# Sheet2_USB-PD.net
KiCad netlist of a schematic drawn in Altium Designer
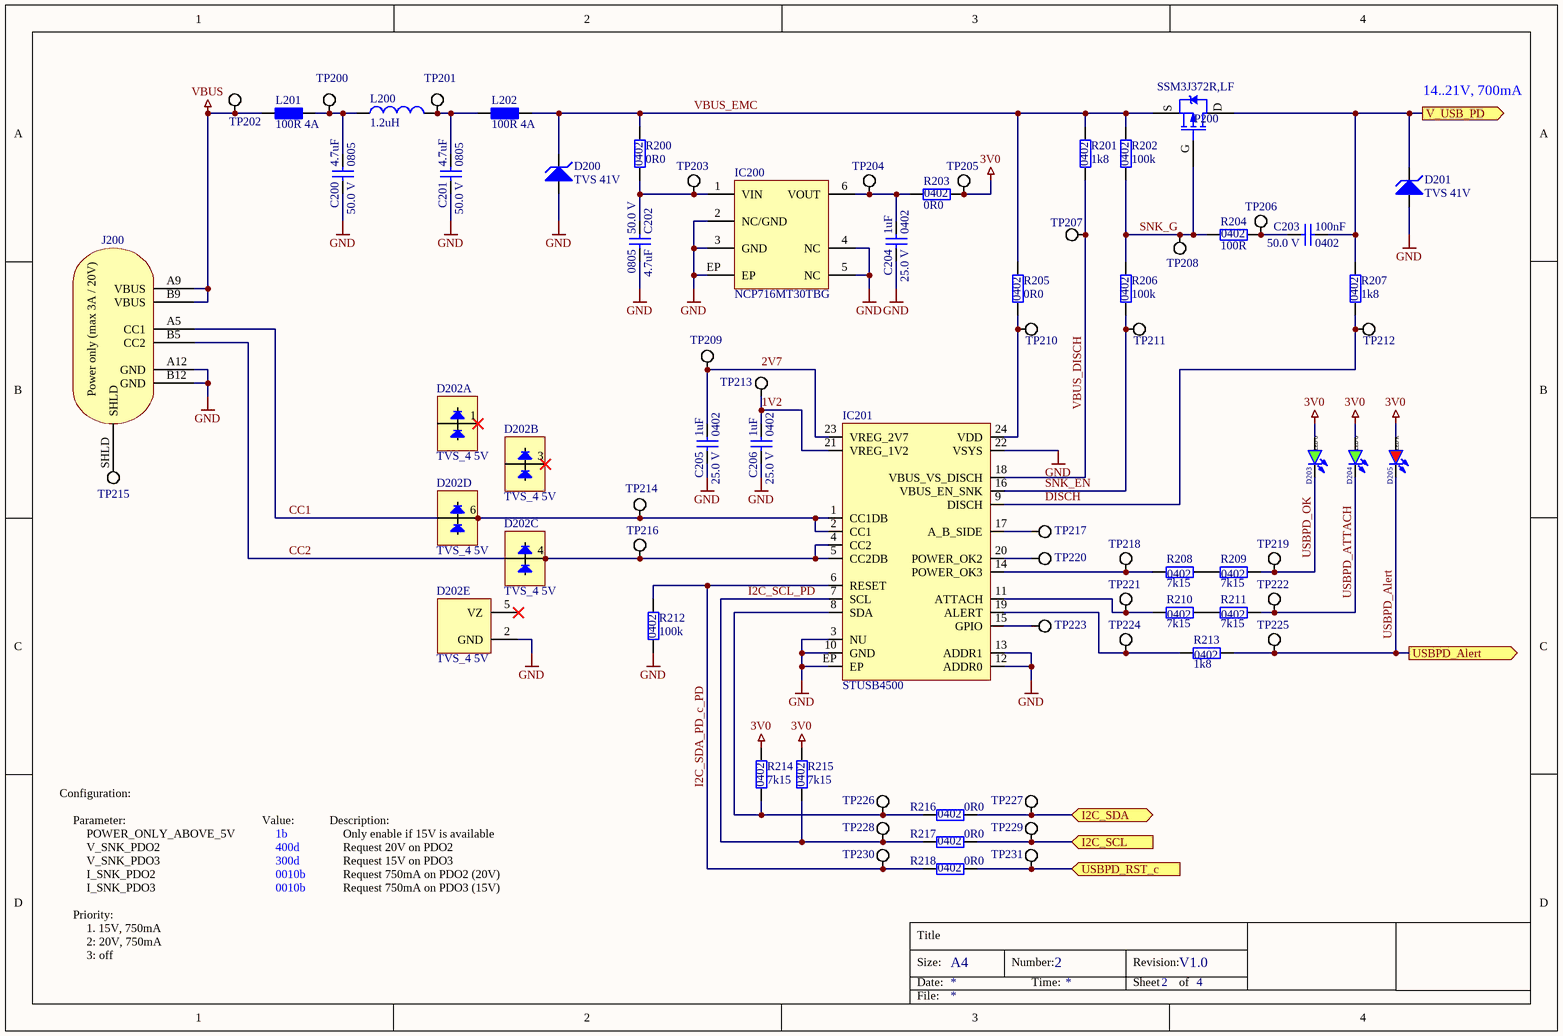
[diagram p0: Sheet2_USB-PD.SchDoc]

(export (version "E")
  (design (tool "Eeschema 10.0.6"))
  (components
    (comp (ref "C200")
      (value "C 4.7uF 0805 50V")
      (footprint "0805")
      (description "CAP CER 4.7UF 50V X5R 0805")
      (fields
        (field (name "MANUFACTURER") "Samsung Electro-Mechanics")
        (field (name "MANUFACTURER PART NUMBER") "CL21A475KBQNNNE")
        (field (name "CAPACITANCE") "4.7uF")
        (field (name "VOLTAGE") "50.0 V")
      )
      (libsource (lib "CS_Part_Library") (part "CAP_4.7uF_50V_0805"))
    )
    (comp (ref "C201")
      (value "C 4.7uF 0805 50V")
      (footprint "0805")
      (description "CAP CER 4.7UF 50V X5R 0805")
      (fields
        (field (name "MANUFACTURER") "Samsung Electro-Mechanics")
        (field (name "MANUFACTURER PART NUMBER") "CL21A475KBQNNNE")
        (field (name "CAPACITANCE") "4.7uF")
        (field (name "VOLTAGE") "50.0 V")
      )
      (libsource (lib "CS_Part_Library") (part "CAP_4.7uF_50V_0805"))
    )
    (comp (ref "C202")
      (value "C 4.7uF 0805 50V")
      (footprint "0805")
      (description "CAP CER 4.7UF 50V X5R 0805")
      (fields
        (field (name "MANUFACTURER") "Samsung Electro-Mechanics")
        (field (name "MANUFACTURER PART NUMBER") "CL21A475KBQNNNE")
        (field (name "CAPACITANCE") "4.7uF")
        (field (name "VOLTAGE") "50.0 V")
      )
      (libsource (lib "CS_Part_Library") (part "CAP_4.7uF_50V_0805"))
    )
    (comp (ref "C203")
      (value "C 100nF 0402 50V")
      (footprint "0402")
      (description "CAP CER 0.1UF 50V X7R 0402")
      (fields
        (field (name "MANUFACTURER") "Murata Electronics")
        (field (name "MANUFACTURER PART NUMBER") "GRM155R71H104KE14J")
        (field (name "CAPACITANCE") "100nF")
        (field (name "VOLTAGE") "50.0 V")
      )
      (libsource (lib "CS_Part_Library") (part "CAP_100nF_50V_0402"))
    )
    (comp (ref "C204")
      (value "C 1uF 0402 25V")
      (footprint "0402")
      (description "CAP CER 1UF 25V X5R 0402")
      (fields
        (field (name "MANUFACTURER") "Taiyo Yuden")
        (field (name "MANUFACTURER PART NUMBER") "TMK105BJ105MV-F")
        (field (name "CAPACITANCE") "1uF")
        (field (name "VOLTAGE") "25.0 V")
      )
      (libsource (lib "CS_Part_Library") (part "CAP_1uF_25V_0402"))
    )
    (comp (ref "C205")
      (value "C 1uF 0402 25V")
      (footprint "0402")
      (description "CAP CER 1UF 25V X5R 0402")
      (fields
        (field (name "MANUFACTURER") "Taiyo Yuden")
        (field (name "MANUFACTURER PART NUMBER") "TMK105BJ105MV-F")
        (field (name "CAPACITANCE") "1uF")
        (field (name "VOLTAGE") "25.0 V")
      )
      (libsource (lib "CS_Part_Library") (part "CAP_1uF_25V_0402"))
    )
    (comp (ref "C206")
      (value "C 1uF 0402 25V")
      (footprint "0402")
      (description "CAP CER 1UF 25V X5R 0402")
      (fields
        (field (name "MANUFACTURER") "Taiyo Yuden")
        (field (name "MANUFACTURER PART NUMBER") "TMK105BJ105MV-F")
        (field (name "CAPACITANCE") "1uF")
        (field (name "VOLTAGE") "25.0 V")
      )
      (libsource (lib "CS_Part_Library") (part "CAP_1uF_25V_0402"))
    )
    (comp (ref "D200")
      (value "TVS 41V")
      (footprint "UDFN-2")
      (description "TVS DIODE 22VWM 41VC 1610")
      (fields
        (field (name "MANUFACTURER") "STMicroelectronics")
        (field (name "MANUFACTURER PART NUMBER") "ESDA25P35-1U1M")
      )
      (libsource (lib "Symbols") (part "D_SCH_41V_35A"))
    )
    (comp (ref "D201")
      (value "TVS 41V")
      (footprint "UDFN-2")
      (description "TVS DIODE 22VWM 41VC 1610")
      (fields
        (field (name "MANUFACTURER") "STMicroelectronics")
        (field (name "MANUFACTURER PART NUMBER") "ESDA25P35-1U1M")
      )
      (libsource (lib "Symbols") (part "D_SCH_41V_35A"))
    )
    (comp (ref "D202")
      (value "TVS_4 5V")
      (footprint "SOT-23-6")
      (description "TVS DIODE 5VWM 12.5VC SOT23-6")
      (fields
        (field (name "MANUFACTURER") "Comchip Technology")
        (field (name "MANUFACTURER PART NUMBER") "CPDT6-5V0UPC-HF")
      )
      (libsource (lib "CS_Part_Library") (part "D_TVS_U4_12V5"))
    )
    (comp (ref "D203")
      (value "LED G")
      (footprint "LED_0603")
      (description "LED GREEN DIFFUSED 0603 SMD")
      (fields
        (field (name "MANUFACTURER") "OSRAM Opto Semiconductors Inc.")
        (field (name "MANUFACTURER PART NUMBER") "LT Q39G-Q1OO-25-1")
      )
      (libsource (lib "CS_Part_Library") (part "D_LED_Green_0603"))
    )
    (comp (ref "D204")
      (value "LED G")
      (footprint "LED_0603")
      (description "LED GREEN DIFFUSED 0603 SMD")
      (fields
        (field (name "MANUFACTURER") "OSRAM Opto Semiconductors Inc.")
        (field (name "MANUFACTURER PART NUMBER") "LT Q39G-Q1OO-25-1")
      )
      (libsource (lib "CS_Part_Library") (part "D_LED_Green_0603"))
    )
    (comp (ref "D205")
      (value "LED R")
      (footprint "LED_0603")
      (description "LED RED DIFFUSED 0603 SMD")
      (fields
        (field (name "MANUFACTURER") "OSRAM Opto Semiconductors Inc.")
        (field (name "MANUFACTURER PART NUMBER") "LS Q976-NR-1")
      )
      (libsource (lib "CS_Part_Library") (part "D_LED_Red_0603"))
    )
    (comp (ref "IC200")
      (value "NCP716MT30TBG")
      (footprint "WDFN-6_EP")
      (description "IC REG LINEAR 3V 80MA 6WDFN")
      (fields (field (name "MANUFACTURER") "onsemi"))
      (libsource (lib "CS_Part_Library") (part "IC_Reg_NCP716MT30TBG"))
    )
    (comp (ref "IC201")
      (value "STUSB4500")
      (footprint "VFQFN-24")
      (description "IC USB CONTROLLER I2C 24QFN")
      (fields
        (field (name "MANUFACTURER") "STMicroelectronics")
        (field (name "MANUFACTURER PART NUMBER") "STUSB4500QTR")
      )
      (libsource (lib "CS_Part_Library") (part "IC_STUSB4500"))
    )
    (comp (ref "J200")
      (value "USB_C PWR")
      (footprint "J_TYPE-C-3_UJC-HP2-3")
      (description "TYPE C, 20 VDC, 3 A, RIGHT ANGLE")
      (fields
        (field (name "MANUFACTURER") "CUI Devices")
        (field (name "MANUFACTURER PART NUMBER") "UJC-HP2-3-SMT-TR")
      )
      (libsource (lib "CS_Part_Library") (part "J_USB-C_3"))
    )
    (comp (ref "L200")
      (value "L 1.2uH 3.9A")
      (footprint "L_3020")
      (description "FIXED IND 1.2UH 3.9A 36 MOHM SMD")
      (fields
        (field (name "MANUFACTURER") "Würth Elektronik")
        (field (name "MANUFACTURER PART NUMBER") "74438336012")
        (field (name "INDUCTANCE") "1.2uH")
      )
      (libsource (lib "CS_Part_Library") (part "L_1.2uH_3.9A"))
    )
    (comp (ref "L201")
      (value "L Ferrite 100R 4A")
      (footprint "L_1206")
      (description "FIXED IND 100 4000MA 1206")
      (fields
        (field (name "MANUFACTURER") "Eaton - Electronics Division")
        (field (name "MANUFACTURER PART NUMBER") "MFBM1V3216-101-R")
        (field (name "INDUCTANCE") "100R 4A")
      )
      (libsource (lib "CS_Part_Library") (part "L_100R_4A"))
    )
    (comp (ref "L202")
      (value "L Ferrite 100R 4A")
      (footprint "L_1206")
      (description "FIXED IND 100 4000MA 1206")
      (fields
        (field (name "MANUFACTURER") "Eaton - Electronics Division")
        (field (name "MANUFACTURER PART NUMBER") "MFBM1V3216-101-R")
        (field (name "INDUCTANCE") "100R 4A")
      )
      (libsource (lib "CS_Part_Library") (part "L_100R_4A"))
    )
    (comp (ref "P200")
      (value "P PMOS 30V 6A")
      (footprint "SOT-23-3-F")
      (description "MOSFET P-CH 30V 6A SOT23F")
      (fields
        (field (name "MANUFACTURER") "Toshiba Semiconductor and Storage")
        (field (name "MANUFACTURER PART NUMBER") "SSM3J372R,LF")
      )
      (libsource (lib "CS_Part_Library") (part "P_PCH_30V_1W"))
    )
    (comp (ref "R200")
      (value "R 0R0 0402")
      (footprint "0402")
      (description "RES 0 OHM JUMPER 1/16W 0402")
      (fields
        (field (name "MANUFACTURER") "Stackpole Electronics Inc")
        (field (name "MANUFACTURER PART NUMBER") "RMCF0402ZT0R00")
        (field (name "RESISTANCE") "0R0")
      )
      (libsource (lib "CS_Part_Library") (part "R_0R0_0402"))
    )
    (comp (ref "R201")
      (value "R 1k8 0402")
      (footprint "0402")
      (description "RES 1.8K OHM 1% 1/16W 0402")
      (fields
        (field (name "MANUFACTURER") "Stackpole Electronics Inc")
        (field (name "MANUFACTURER PART NUMBER") "RMCF0402FT1K80")
        (field (name "RESISTANCE") "1k8")
      )
      (libsource (lib "CS_Part_Library") (part "R_1k8_0402"))
    )
    (comp (ref "R202")
      (value "R 100k 0402")
      (footprint "0402")
      (description "RES 100K OHM 5% 1/16W 0402")
      (fields
        (field (name "MANUFACTURER") "YAGEO")
        (field (name "MANUFACTURER PART NUMBER") "RC0402JR-07100KL")
        (field (name "RESISTANCE") "100k")
      )
      (libsource (lib "CS_Part_Library") (part "R_100k_0402"))
    )
    (comp (ref "R203")
      (value "R 0R0 0402")
      (footprint "0402")
      (description "RES 0 OHM JUMPER 1/16W 0402")
      (fields
        (field (name "MANUFACTURER") "Stackpole Electronics Inc")
        (field (name "MANUFACTURER PART NUMBER") "RMCF0402ZT0R00")
        (field (name "RESISTANCE") "0R0")
      )
      (libsource (lib "") (part "R_0R0_0402_1"))
    )
    (comp (ref "R204")
      (value "R 100R 0402")
      (footprint "0402")
      (description "RES 100 OHM 1% 1/16W 0402")
      (fields
        (field (name "MANUFACTURER") "Stackpole Electronics Inc")
        (field (name "MANUFACTURER PART NUMBER") "RMCF0402FT100R")
        (field (name "RESISTANCE") "100R")
      )
      (libsource (lib "CS_Part_Library") (part "R_100R_0402"))
    )
    (comp (ref "R205")
      (value "R 0R0 0402")
      (footprint "0402")
      (description "RES 0 OHM JUMPER 1/16W 0402")
      (fields
        (field (name "MANUFACTURER") "Stackpole Electronics Inc")
        (field (name "MANUFACTURER PART NUMBER") "RMCF0402ZT0R00")
        (field (name "RESISTANCE") "0R0")
      )
      (libsource (lib "CS_Part_Library") (part "R_0R0_0402"))
    )
    (comp (ref "R206")
      (value "R 100k 0402")
      (footprint "0402")
      (description "RES 100K OHM 5% 1/16W 0402")
      (fields
        (field (name "MANUFACTURER") "YAGEO")
        (field (name "MANUFACTURER PART NUMBER") "RC0402JR-07100KL")
        (field (name "RESISTANCE") "100k")
      )
      (libsource (lib "CS_Part_Library") (part "R_100k_0402"))
    )
    (comp (ref "R207")
      (value "R 1k8 0402")
      (footprint "0402")
      (description "RES 1.8K OHM 1% 1/16W 0402")
      (fields
        (field (name "MANUFACTURER") "Stackpole Electronics Inc")
        (field (name "MANUFACTURER PART NUMBER") "RMCF0402FT1K80")
        (field (name "RESISTANCE") "1k8")
      )
      (libsource (lib "CS_Part_Library") (part "R_1k8_0402"))
    )
    (comp (ref "R208")
      (value "R 7k15 0402")
      (footprint "0402")
      (description "RES 7.15K OHM 1% 1/16W 0402")
      (fields
        (field (name "MANUFACTURER") "Stackpole Electronics Inc")
        (field (name "MANUFACTURER PART NUMBER") "RMCF0402FT7K15")
        (field (name "RESISTANCE") "7k15")
      )
      (libsource (lib "CS_Part_Library") (part "R_7k15_0402"))
    )
    (comp (ref "R209")
      (value "R 7k15 0402")
      (footprint "0402")
      (description "RES 7.15K OHM 1% 1/16W 0402")
      (fields
        (field (name "MANUFACTURER") "Stackpole Electronics Inc")
        (field (name "MANUFACTURER PART NUMBER") "RMCF0402FT7K15")
        (field (name "RESISTANCE") "7k15")
      )
      (libsource (lib "CS_Part_Library") (part "R_7k15_0402"))
    )
    (comp (ref "R210")
      (value "R 7k15 0402")
      (footprint "0402")
      (description "RES 7.15K OHM 1% 1/16W 0402")
      (fields
        (field (name "MANUFACTURER") "Stackpole Electronics Inc")
        (field (name "MANUFACTURER PART NUMBER") "RMCF0402FT7K15")
        (field (name "RESISTANCE") "7k15")
      )
      (libsource (lib "CS_Part_Library") (part "R_7k15_0402"))
    )
    (comp (ref "R211")
      (value "R 7k15 0402")
      (footprint "0402")
      (description "RES 7.15K OHM 1% 1/16W 0402")
      (fields
        (field (name "MANUFACTURER") "Stackpole Electronics Inc")
        (field (name "MANUFACTURER PART NUMBER") "RMCF0402FT7K15")
        (field (name "RESISTANCE") "7k15")
      )
      (libsource (lib "CS_Part_Library") (part "R_7k15_0402"))
    )
    (comp (ref "R212")
      (value "R 100k 0402")
      (footprint "0402")
      (description "RES 100K OHM 5% 1/16W 0402")
      (fields
        (field (name "MANUFACTURER") "YAGEO")
        (field (name "MANUFACTURER PART NUMBER") "RC0402JR-07100KL")
        (field (name "RESISTANCE") "100k")
      )
      (libsource (lib "CS_Part_Library") (part "R_100k_0402"))
    )
    (comp (ref "R213")
      (value "R 1k8 0402")
      (footprint "0402")
      (description "RES 1.8K OHM 1% 1/16W 0402")
      (fields
        (field (name "MANUFACTURER") "Stackpole Electronics Inc")
        (field (name "MANUFACTURER PART NUMBER") "RMCF0402FT1K80")
        (field (name "RESISTANCE") "1k8")
      )
      (libsource (lib "") (part "R_1k8_0402_1"))
    )
    (comp (ref "R214")
      (value "R 7k15 0402")
      (footprint "0402")
      (description "RES 7.15K OHM 1% 1/16W 0402")
      (fields
        (field (name "MANUFACTURER") "Stackpole Electronics Inc")
        (field (name "MANUFACTURER PART NUMBER") "RMCF0402FT7K15")
        (field (name "RESISTANCE") "7k15")
      )
      (libsource (lib "") (part "R_7k15_0402_1"))
    )
    (comp (ref "R215")
      (value "R 7k15 0402")
      (footprint "0402")
      (description "RES 7.15K OHM 1% 1/16W 0402")
      (fields
        (field (name "MANUFACTURER") "Stackpole Electronics Inc")
        (field (name "MANUFACTURER PART NUMBER") "RMCF0402FT7K15")
        (field (name "RESISTANCE") "7k15")
      )
      (libsource (lib "") (part "R_7k15_0402_1"))
    )
    (comp (ref "R216")
      (value "R 0R0 0402")
      (footprint "0402")
      (description "RES 0 OHM JUMPER 1/16W 0402")
      (fields
        (field (name "MANUFACTURER") "Stackpole Electronics Inc")
        (field (name "MANUFACTURER PART NUMBER") "RMCF0402ZT0R00")
        (field (name "RESISTANCE") "0R0")
      )
      (libsource (lib "") (part "R_0R0_0402_1"))
    )
    (comp (ref "R217")
      (value "R 0R0 0402")
      (footprint "0402")
      (description "RES 0 OHM JUMPER 1/16W 0402")
      (fields
        (field (name "MANUFACTURER") "Stackpole Electronics Inc")
        (field (name "MANUFACTURER PART NUMBER") "RMCF0402ZT0R00")
        (field (name "RESISTANCE") "0R0")
      )
      (libsource (lib "") (part "R_0R0_0402_1"))
    )
    (comp (ref "R218")
      (value "R 0R0 0402")
      (footprint "0402")
      (description "RES 0 OHM JUMPER 1/16W 0402")
      (fields
        (field (name "MANUFACTURER") "Stackpole Electronics Inc")
        (field (name "MANUFACTURER PART NUMBER") "RMCF0402ZT0R00")
        (field (name "RESISTANCE") "0R0")
      )
      (libsource (lib "") (part "R_0R0_0402_1"))
    )
    (comp (ref "TP200")
      (value "TP")
      (footprint "TP_1mm")
      (description "Test Point 1mm")
      (libsource (lib "Symbols") (part "TP_1mm"))
    )
    (comp (ref "TP201")
      (value "TP")
      (footprint "TP_1mm")
      (description "Test Point 1mm")
      (libsource (lib "Symbols") (part "TP_1mm"))
    )
    (comp (ref "TP202")
      (value "TP")
      (footprint "TP_1mm")
      (description "Test Point 1mm")
      (libsource (lib "CS_Part_Library") (part "TP_1mm"))
    )
    (comp (ref "TP203")
      (value "TP")
      (footprint "TP_1mm")
      (description "Test Point 1mm")
      (libsource (lib "CS_Part_Library") (part "TP_1mm"))
    )
    (comp (ref "TP204")
      (value "TP")
      (footprint "TP_1mm")
      (description "Test Point 1mm")
      (libsource (lib "CS_Part_Library") (part "TP_1mm"))
    )
    (comp (ref "TP205")
      (value "TP")
      (footprint "TP_1mm")
      (description "Test Point 1mm")
      (libsource (lib "CS_Part_Library") (part "TP_1mm"))
    )
    (comp (ref "TP206")
      (value "TP")
      (footprint "TP_1mm")
      (description "Test Point 1mm")
      (libsource (lib "CS_Part_Library") (part "TP_1mm"))
    )
    (comp (ref "TP207")
      (value "TP")
      (footprint "TP_1mm")
      (description "Test Point 1mm")
      (libsource (lib "CS_Part_Library") (part "TP_1mm"))
    )
    (comp (ref "TP208")
      (value "TP")
      (footprint "TP_1mm")
      (description "Test Point 1mm")
      (libsource (lib "CS_Part_Library") (part "TP_1mm"))
    )
    (comp (ref "TP209")
      (value "TP")
      (footprint "TP_1mm")
      (description "Test Point 1mm")
      (libsource (lib "CS_Part_Library") (part "TP_1mm"))
    )
    (comp (ref "TP210")
      (value "TP")
      (footprint "TP_1mm")
      (description "Test Point 1mm")
      (libsource (lib "CS_Part_Library") (part "TP_1mm"))
    )
    (comp (ref "TP211")
      (value "TP")
      (footprint "TP_1mm")
      (description "Test Point 1mm")
      (libsource (lib "CS_Part_Library") (part "TP_1mm"))
    )
    (comp (ref "TP212")
      (value "TP")
      (footprint "TP_1mm")
      (description "Test Point 1mm")
      (libsource (lib "CS_Part_Library") (part "TP_1mm"))
    )
    (comp (ref "TP213")
      (value "TP")
      (footprint "TP_1mm")
      (description "Test Point 1mm")
      (libsource (lib "CS_Part_Library") (part "TP_1mm"))
    )
    (comp (ref "TP214")
      (value "TP")
      (footprint "TP_1mm")
      (description "Test Point 1mm")
      (libsource (lib "CS_Part_Library") (part "TP_1mm"))
    )
    (comp (ref "TP215")
      (value "TP")
      (footprint "TP_1mm")
      (description "Test Point 1mm")
      (libsource (lib "CS_Part_Library") (part "TP_1mm"))
    )
    (comp (ref "TP216")
      (value "TP")
      (footprint "TP_1mm")
      (description "Test Point 1mm")
      (libsource (lib "CS_Part_Library") (part "TP_1mm"))
    )
    (comp (ref "TP217")
      (value "TP")
      (footprint "TP_1mm")
      (description "Test Point 1mm")
      (libsource (lib "CS_Part_Library") (part "TP_1mm"))
    )
    (comp (ref "TP218")
      (value "TP")
      (footprint "TP_1mm")
      (description "Test Point 1mm")
      (libsource (lib "CS_Part_Library") (part "TP_1mm"))
    )
    (comp (ref "TP219")
      (value "TP")
      (footprint "TP_1mm")
      (description "Test Point 1mm")
      (libsource (lib "CS_Part_Library") (part "TP_1mm"))
    )
    (comp (ref "TP220")
      (value "TP")
      (footprint "TP_1mm")
      (description "Test Point 1mm")
      (libsource (lib "CS_Part_Library") (part "TP_1mm"))
    )
    (comp (ref "TP221")
      (value "TP")
      (footprint "TP_1mm")
      (description "Test Point 1mm")
      (libsource (lib "CS_Part_Library") (part "TP_1mm"))
    )
    (comp (ref "TP222")
      (value "TP")
      (footprint "TP_1mm")
      (description "Test Point 1mm")
      (libsource (lib "CS_Part_Library") (part "TP_1mm"))
    )
    (comp (ref "TP223")
      (value "TP")
      (footprint "TP_1mm")
      (description "Test Point 1mm")
      (libsource (lib "CS_Part_Library") (part "TP_1mm"))
    )
    (comp (ref "TP224")
      (value "TP")
      (footprint "TP_1mm")
      (description "Test Point 1mm")
      (libsource (lib "CS_Part_Library") (part "TP_1mm"))
    )
    (comp (ref "TP225")
      (value "TP")
      (footprint "TP_1mm")
      (description "Test Point 1mm")
      (libsource (lib "CS_Part_Library") (part "TP_1mm"))
    )
    (comp (ref "TP226")
      (value "TP")
      (footprint "TP_1mm")
      (description "Test Point 1mm")
      (libsource (lib "CS_Part_Library") (part "TP_1mm"))
    )
    (comp (ref "TP227")
      (value "TP")
      (footprint "TP_1mm")
      (description "Test Point 1mm")
      (libsource (lib "CS_Part_Library") (part "TP_1mm"))
    )
    (comp (ref "TP228")
      (value "TP")
      (footprint "TP_1mm")
      (description "Test Point 1mm")
      (libsource (lib "CS_Part_Library") (part "TP_1mm"))
    )
    (comp (ref "TP229")
      (value "TP")
      (footprint "TP_1mm")
      (description "Test Point 1mm")
      (libsource (lib "CS_Part_Library") (part "TP_1mm"))
    )
    (comp (ref "TP230")
      (value "TP")
      (footprint "TP_1mm")
      (description "Test Point 1mm")
      (libsource (lib "CS_Part_Library") (part "TP_1mm"))
    )
    (comp (ref "TP231")
      (value "TP")
      (footprint "TP_1mm")
      (description "Test Point 1mm")
      (libsource (lib "CS_Part_Library") (part "TP_1mm"))
    )
  )
  (nets
    (net (code "1") (name "/1V2") (class "Default")
      (node (ref "C206") (pin "2") (pinfunction "2_2") (pintype "passive"))
      (node (ref "IC201") (pin "21") (pinfunction "VREG_1V2_21") (pintype "passive"))
      (node (ref "TP213") (pin "1") (pinfunction "TP_1") (pintype "passive"))
    )
    (net (code "2") (name "/2V7") (class "Default")
      (node (ref "C205") (pin "2") (pinfunction "2_2") (pintype "passive"))
      (node (ref "IC201") (pin "23") (pinfunction "VREG_2V7_23") (pintype "passive"))
      (node (ref "TP209") (pin "1") (pinfunction "TP_1") (pintype "passive"))
    )
    (net (code "3") (name "/CC1") (class "Default")
      (node (ref "D202") (pin "6") (pinfunction "6_6") (pintype "passive"))
      (node (ref "IC201") (pin "1") (pinfunction "CC1DB_1") (pintype "passive"))
      (node (ref "IC201") (pin "2") (pinfunction "CC1_2") (pintype "passive"))
      (node (ref "J200") (pin "A5") (pinfunction "CC1_A5") (pintype "passive"))
      (node (ref "TP214") (pin "1") (pinfunction "TP_1") (pintype "passive"))
    )
    (net (code "4") (name "/CC2") (class "Default")
      (node (ref "D202") (pin "4") (pinfunction "4_4") (pintype "passive"))
      (node (ref "IC201") (pin "4") (pinfunction "CC2_4") (pintype "passive"))
      (node (ref "IC201") (pin "5") (pinfunction "CC2DB_5") (pintype "passive"))
      (node (ref "J200") (pin "B5") (pinfunction "CC2_B5") (pintype "passive"))
      (node (ref "TP216") (pin "1") (pinfunction "TP_1") (pintype "passive"))
    )
    (net (code "5") (name "/DISCH") (class "Default")
      (node (ref "IC201") (pin "9") (pinfunction "DISCH_9") (pintype "passive"))
      (node (ref "R207") (pin "1") (pinfunction "1_1") (pintype "passive"))
      (node (ref "TP212") (pin "1") (pinfunction "TP_1") (pintype "passive"))
    )
    (net (code "6") (name "/I2C_SCL") (class "Default")
      (node (ref "R217") (pin "2") (pinfunction "2_2") (pintype "passive"))
      (node (ref "TP229") (pin "1") (pinfunction "TP_1") (pintype "passive"))
    )
    (net (code "7") (name "/I2C_SCL_PD") (class "Default")
      (node (ref "IC201") (pin "7") (pinfunction "SCL_7") (pintype "passive"))
      (node (ref "R215") (pin "1") (pinfunction "1_1") (pintype "passive"))
      (node (ref "R217") (pin "1") (pinfunction "1_1") (pintype "passive"))
      (node (ref "TP228") (pin "1") (pinfunction "TP_1") (pintype "passive"))
    )
    (net (code "8") (name "/I2C_SDA") (class "Default")
      (node (ref "R216") (pin "2") (pinfunction "2_2") (pintype "passive"))
      (node (ref "TP227") (pin "1") (pinfunction "TP_1") (pintype "passive"))
    )
    (net (code "9") (name "/I2C_SDA_PD_c_PD") (class "Default")
      (node (ref "IC201") (pin "6") (pinfunction "RESET_6") (pintype "passive"))
      (node (ref "R212") (pin "2") (pinfunction "2_2") (pintype "passive"))
      (node (ref "R218") (pin "1") (pinfunction "1_1") (pintype "passive"))
      (node (ref "TP230") (pin "1") (pinfunction "TP_1") (pintype "passive"))
    )
    (net (code "10") (name "/SNK_EN") (class "Default")
      (node (ref "IC201") (pin "16") (pinfunction "VBUS_EN_SNK_16") (pintype "passive"))
      (node (ref "R206") (pin "1") (pinfunction "1_1") (pintype "passive"))
      (node (ref "TP211") (pin "1") (pinfunction "TP_1") (pintype "passive"))
    )
    (net (code "11") (name "/SNK_G") (class "Default")
      (node (ref "P200") (pin "1") (pinfunction "G_1") (pintype "passive"))
      (node (ref "R202") (pin "1") (pinfunction "1_1") (pintype "passive"))
      (node (ref "R204") (pin "1") (pinfunction "1_1") (pintype "passive"))
      (node (ref "R206") (pin "2") (pinfunction "2_2") (pintype "passive"))
      (node (ref "TP208") (pin "1") (pinfunction "TP_1") (pintype "passive"))
    )
    (net (code "12") (name "/USBPD_ATTACH") (class "Default")
      (node (ref "D204") (pin "K") (pinfunction "K_K") (pintype "passive"))
      (node (ref "R211") (pin "1") (pinfunction "1_1") (pintype "passive"))
      (node (ref "TP222") (pin "1") (pinfunction "TP_1") (pintype "passive"))
    )
    (net (code "13") (name "/USBPD_Alert") (class "Default")
      (node (ref "D205") (pin "K") (pinfunction "K_K") (pintype "passive"))
      (node (ref "R213") (pin "1") (pinfunction "1_1") (pintype "passive"))
      (node (ref "TP225") (pin "1") (pinfunction "TP_1") (pintype "passive"))
    )
    (net (code "14") (name "/USBPD_OK") (class "Default")
      (node (ref "D203") (pin "K") (pinfunction "K_K") (pintype "passive"))
      (node (ref "R209") (pin "1") (pinfunction "1_1") (pintype "passive"))
      (node (ref "TP219") (pin "1") (pinfunction "TP_1") (pintype "passive"))
    )
    (net (code "15") (name "/USBPD_RST_c") (class "Default")
      (node (ref "R218") (pin "2") (pinfunction "2_2") (pintype "passive"))
      (node (ref "TP231") (pin "1") (pinfunction "TP_1") (pintype "passive"))
    )
    (net (code "16") (name "/VBUS_DISCH") (class "Default")
      (node (ref "IC201") (pin "18") (pinfunction "VBUS_VS_DISCH_18") (pintype "passive"))
      (node (ref "R201") (pin "1") (pinfunction "1_1") (pintype "passive"))
      (node (ref "TP207") (pin "1") (pinfunction "TP_1") (pintype "passive"))
    )
    (net (code "17") (name "/VBUS_EMC") (class "Default")
      (node (ref "D200") (pin "1") (pinfunction "K_1") (pintype "passive"))
      (node (ref "L202") (pin "2") (pinfunction "2_2") (pintype "passive"))
      (node (ref "P200") (pin "2") (pinfunction "S_2") (pintype "passive"))
      (node (ref "R200") (pin "2") (pinfunction "2_2") (pintype "passive"))
      (node (ref "R201") (pin "2") (pinfunction "2_2") (pintype "passive"))
      (node (ref "R202") (pin "2") (pinfunction "2_2") (pintype "passive"))
      (node (ref "R205") (pin "2") (pinfunction "2_2") (pintype "passive"))
    )
    (net (code "18") (name "/V_USB_PD") (class "Default")
      (node (ref "C203") (pin "2") (pinfunction "2_2") (pintype "passive"))
      (node (ref "D201") (pin "1") (pinfunction "K_1") (pintype "passive"))
      (node (ref "P200") (pin "3") (pinfunction "D_3") (pintype "passive"))
      (node (ref "R207") (pin "2") (pinfunction "2_2") (pintype "passive"))
    )
    (net (code "19") (name "3V0") (class "Default")
      (node (ref "D203") (pin "A") (pinfunction "A_A") (pintype "passive"))
      (node (ref "D204") (pin "A") (pinfunction "A_A") (pintype "passive"))
      (node (ref "D205") (pin "A") (pinfunction "A_A") (pintype "passive"))
      (node (ref "R203") (pin "2") (pinfunction "2_2") (pintype "passive"))
      (node (ref "R214") (pin "2") (pinfunction "2_2") (pintype "passive"))
      (node (ref "R215") (pin "2") (pinfunction "2_2") (pintype "passive"))
      (node (ref "TP205") (pin "1") (pinfunction "TP_1") (pintype "passive"))
    )
    (net (code "20") (name "GND") (class "Default")
      (node (ref "C200") (pin "1") (pinfunction "1_1") (pintype "passive"))
      (node (ref "C201") (pin "1") (pinfunction "1_1") (pintype "passive"))
      (node (ref "C202") (pin "2") (pinfunction "2_2") (pintype "passive"))
      (node (ref "C204") (pin "1") (pinfunction "1_1") (pintype "passive"))
      (node (ref "C205") (pin "1") (pinfunction "1_1") (pintype "passive"))
      (node (ref "C206") (pin "1") (pinfunction "1_1") (pintype "passive"))
      (node (ref "D200") (pin "2") (pinfunction "A_2") (pintype "passive"))
      (node (ref "D201") (pin "2") (pinfunction "A_2") (pintype "passive"))
      (node (ref "D202") (pin "2") (pinfunction "GND_2") (pintype "passive"))
      (node (ref "IC200") (pin "2") (pinfunction "NC/GND_2") (pintype "passive"))
      (node (ref "IC200") (pin "3") (pinfunction "GND_3") (pintype "passive"))
      (node (ref "IC200") (pin "4") (pinfunction "NC_4") (pintype "passive"))
      (node (ref "IC200") (pin "5") (pinfunction "NC_5") (pintype "passive"))
      (node (ref "IC200") (pin "EP") (pinfunction "EP_EP") (pintype "passive"))
      (node (ref "IC201") (pin "10") (pinfunction "GND_10") (pintype "passive"))
      (node (ref "IC201") (pin "12") (pinfunction "ADDR0_12") (pintype "passive"))
      (node (ref "IC201") (pin "13") (pinfunction "ADDR1_13") (pintype "passive"))
      (node (ref "IC201") (pin "22") (pinfunction "VSYS_22") (pintype "passive"))
      (node (ref "IC201") (pin "3") (pinfunction "NU_3") (pintype "passive"))
      (node (ref "IC201") (pin "EP") (pinfunction "EP_EP") (pintype "passive"))
      (node (ref "J200") (pin "A12") (pinfunction "GND_A12") (pintype "passive"))
      (node (ref "J200") (pin "B12") (pinfunction "GND_B12") (pintype "passive"))
      (node (ref "R212") (pin "1") (pinfunction "1_1") (pintype "passive"))
    )
    (net (code "21") (name "Net-(IC200-VIN)") (class "Default")
      (node (ref "C202") (pin "1") (pinfunction "1_1") (pintype "passive"))
      (node (ref "IC200") (pin "1") (pinfunction "VIN_1") (pintype "passive"))
      (node (ref "R200") (pin "1") (pinfunction "1_1") (pintype "passive"))
      (node (ref "TP203") (pin "1") (pinfunction "TP_1") (pintype "passive"))
    )
    (net (code "22") (name "Net-(IC200-VOUT)") (class "Default")
      (node (ref "C204") (pin "2") (pinfunction "2_2") (pintype "passive"))
      (node (ref "IC200") (pin "6") (pinfunction "VOUT_6") (pintype "passive"))
      (node (ref "R203") (pin "1") (pinfunction "1_1") (pintype "passive"))
      (node (ref "TP204") (pin "1") (pinfunction "TP_1") (pintype "passive"))
    )
    (net (code "23") (name "Net-(IC201-ALERT)") (class "Default")
      (node (ref "IC201") (pin "19") (pinfunction "ALERT_19") (pintype "passive"))
      (node (ref "R213") (pin "2") (pinfunction "2_2") (pintype "passive"))
      (node (ref "TP224") (pin "1") (pinfunction "TP_1") (pintype "passive"))
    )
    (net (code "24") (name "Net-(IC201-ATTACH)") (class "Default")
      (node (ref "IC201") (pin "11") (pinfunction "ATTACH_11") (pintype "passive"))
      (node (ref "R210") (pin "2") (pinfunction "2_2") (pintype "passive"))
      (node (ref "TP221") (pin "1") (pinfunction "TP_1") (pintype "passive"))
    )
    (net (code "25") (name "Net-(IC201-A_B_SIDE)") (class "Default")
      (node (ref "IC201") (pin "17") (pinfunction "A_B_SIDE_17") (pintype "passive"))
      (node (ref "TP217") (pin "1") (pinfunction "TP_1") (pintype "passive"))
    )
    (net (code "26") (name "Net-(IC201-GPIO)") (class "Default")
      (node (ref "IC201") (pin "15") (pinfunction "GPIO_15") (pintype "passive"))
      (node (ref "TP223") (pin "1") (pinfunction "TP_1") (pintype "passive"))
    )
    (net (code "27") (name "Net-(IC201-POWER_OK2)") (class "Default")
      (node (ref "IC201") (pin "20") (pinfunction "POWER_OK2_20") (pintype "passive"))
      (node (ref "TP220") (pin "1") (pinfunction "TP_1") (pintype "passive"))
    )
    (net (code "28") (name "Net-(IC201-POWER_OK3)") (class "Default")
      (node (ref "IC201") (pin "14") (pinfunction "POWER_OK3_14") (pintype "passive"))
      (node (ref "R208") (pin "2") (pinfunction "2_2") (pintype "passive"))
      (node (ref "TP218") (pin "1") (pinfunction "TP_1") (pintype "passive"))
    )
    (net (code "29") (name "Net-(IC201-SDA)") (class "Default")
      (node (ref "IC201") (pin "8") (pinfunction "SDA_8") (pintype "passive"))
      (node (ref "R214") (pin "1") (pinfunction "1_1") (pintype "passive"))
      (node (ref "R216") (pin "1") (pinfunction "1_1") (pintype "passive"))
      (node (ref "TP226") (pin "1") (pinfunction "TP_1") (pintype "passive"))
    )
    (net (code "30") (name "Net-(IC201-VDD)") (class "Default")
      (node (ref "IC201") (pin "24") (pinfunction "VDD_24") (pintype "passive"))
      (node (ref "R205") (pin "1") (pinfunction "1_1") (pintype "passive"))
      (node (ref "TP210") (pin "1") (pinfunction "TP_1") (pintype "passive"))
    )
    (net (code "31") (name "Net-(R208-Pad1)") (class "Default")
      (node (ref "R208") (pin "1") (pinfunction "1_1") (pintype "passive"))
      (node (ref "R209") (pin "2") (pinfunction "2_2") (pintype "passive"))
    )
    (net (code "32") (name "Net-(R210-Pad1)") (class "Default")
      (node (ref "R210") (pin "1") (pinfunction "1_1") (pintype "passive"))
      (node (ref "R211") (pin "2") (pinfunction "2_2") (pintype "passive"))
    )
    (net (code "33") (name "Net-(TP200-TP)") (class "Default")
      (node (ref "C200") (pin "2") (pinfunction "2_2") (pintype "passive"))
      (node (ref "L200") (pin "1") (pinfunction "1_1") (pintype "passive"))
      (node (ref "L201") (pin "2") (pinfunction "2_2") (pintype "passive"))
      (node (ref "TP200") (pin "1") (pinfunction "TP_1") (pintype "passive"))
    )
    (net (code "34") (name "Net-(TP201-TP)") (class "Default")
      (node (ref "C201") (pin "2") (pinfunction "2_2") (pintype "passive"))
      (node (ref "L200") (pin "2") (pinfunction "2_2") (pintype "passive"))
      (node (ref "L202") (pin "1") (pinfunction "1_1") (pintype "passive"))
      (node (ref "TP201") (pin "1") (pinfunction "TP_1") (pintype "passive"))
    )
    (net (code "35") (name "Net-(TP206-TP)") (class "Default")
      (node (ref "C203") (pin "1") (pinfunction "1_1") (pintype "passive"))
      (node (ref "R204") (pin "2") (pinfunction "2_2") (pintype "passive"))
      (node (ref "TP206") (pin "1") (pinfunction "TP_1") (pintype "passive"))
    )
    (net (code "36") (name "Net-(TP215-TP)") (class "Default")
      (node (ref "J200") (pin "SHLD") (pinfunction "SHLD_SHLD") (pintype "passive"))
      (node (ref "TP215") (pin "1") (pinfunction "TP_1") (pintype "passive"))
    )
    (net (code "37") (name "VBUS") (class "Default")
      (node (ref "J200") (pin "A9") (pinfunction "VBUS_A9") (pintype "passive"))
      (node (ref "J200") (pin "B9") (pinfunction "VBUS_B9") (pintype "passive"))
      (node (ref "L201") (pin "1") (pinfunction "1_1") (pintype "passive"))
      (node (ref "TP202") (pin "1") (pinfunction "TP_1") (pintype "passive"))
    )
    (net (code "38") (name "unconnected-(D202-Pad1)") (class "Default")
      (node (ref "D202") (pin "1") (pinfunction "1_1") (pintype "passive+no_connect"))
    )
    (net (code "39") (name "unconnected-(D202-Pad3)") (class "Default")
      (node (ref "D202") (pin "3") (pinfunction "3_3") (pintype "passive+no_connect"))
    )
    (net (code "40") (name "unconnected-(D202E-VZ-Pad5)") (class "Default")
      (node (ref "D202") (pin "5") (pinfunction "VZ_5") (pintype "passive+no_connect"))
    )
  )
)
